# Carloop2-v3_1.net
KiCad netlist of a schematic drawn in EAGLE
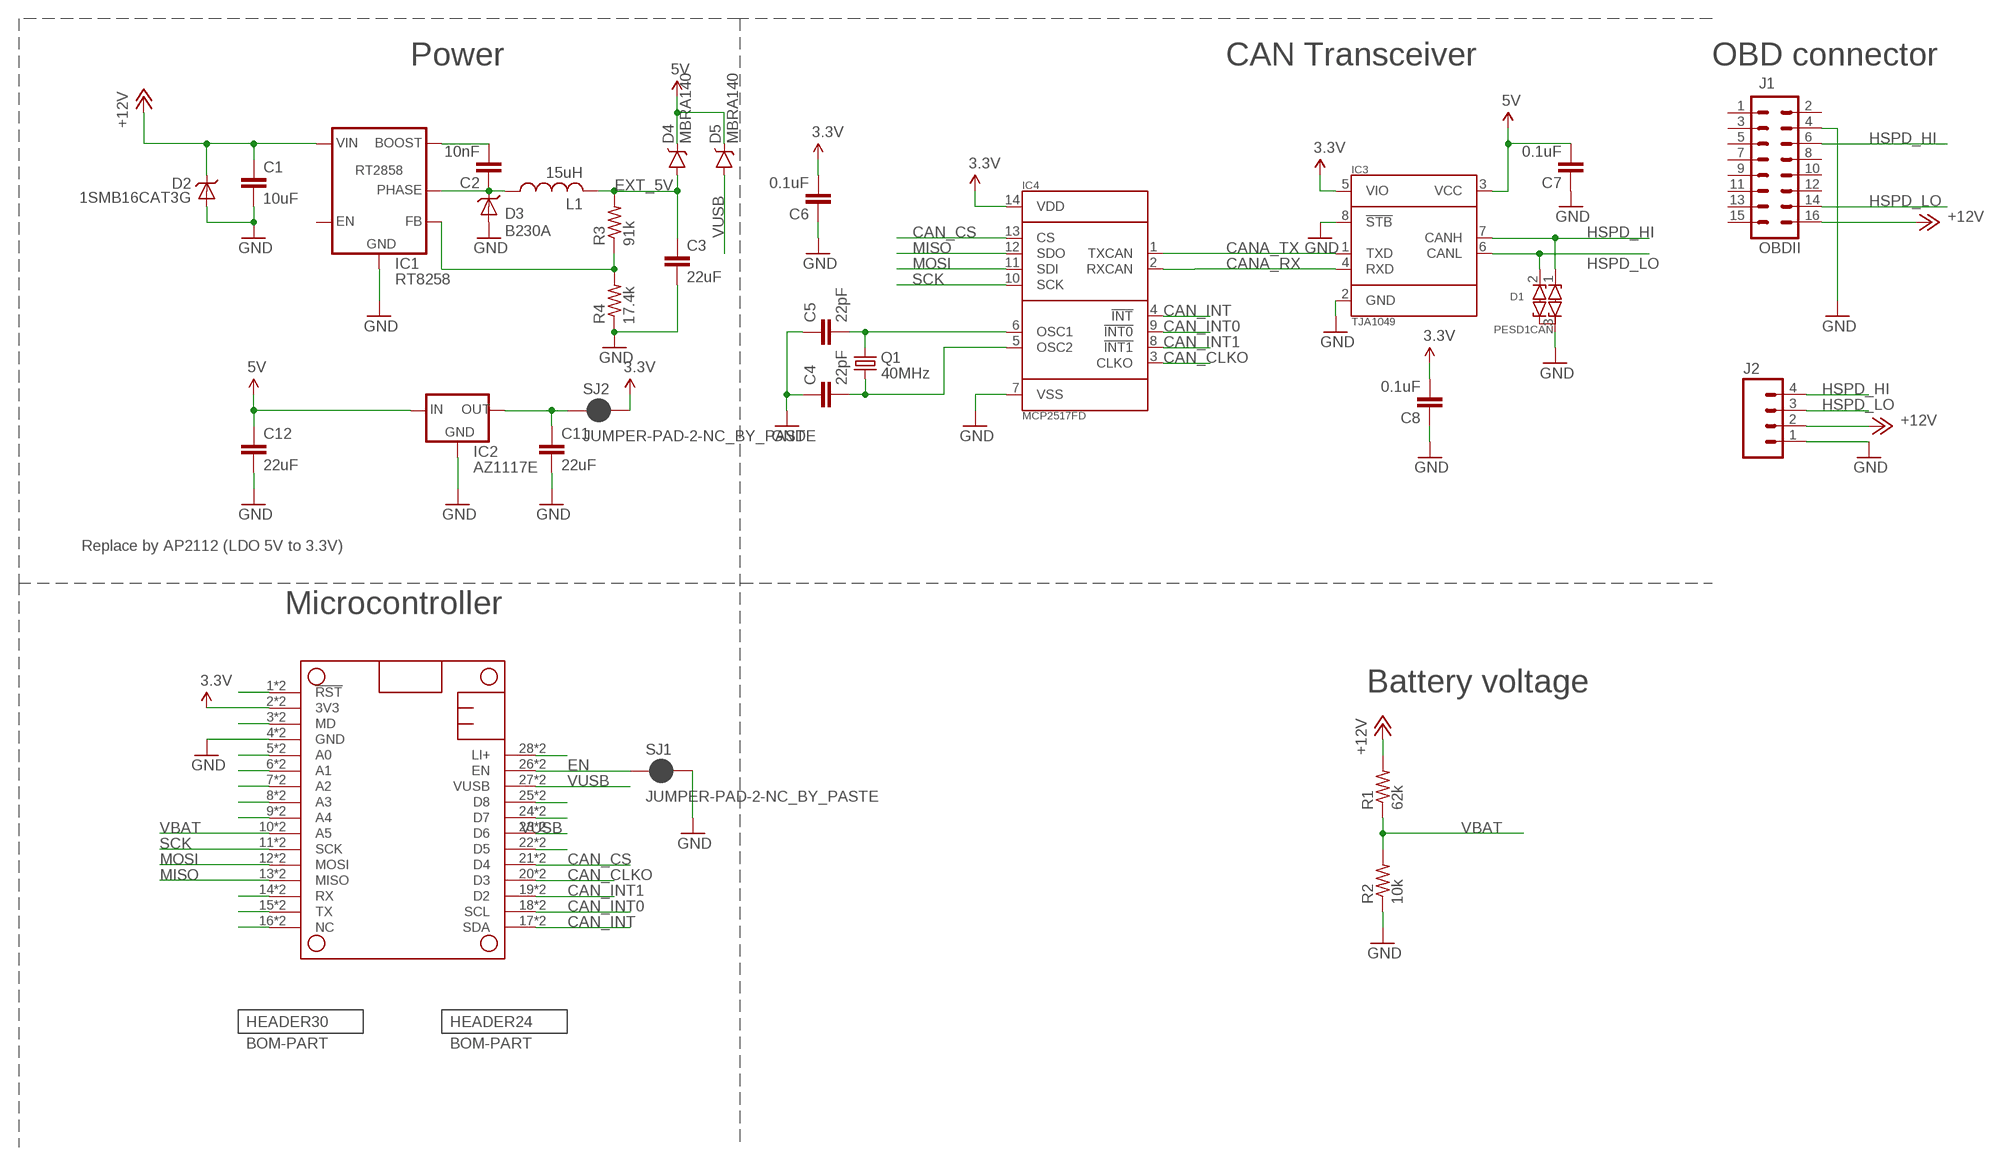
[diagram p0: schematic, sheet 1]

(export (version "E")
  (design (tool "Eeschema 10.0.6"))
  (components
    (comp (ref "C1")
      (value "10uF")
      (footprint "eagle-import:C1206")
      (fields (field (name "PARTNO") "C3216X7R1E106K160AB"))
      (libsource (lib "eagle-import") (part "C-EUC1206"))
    )
    (comp (ref "C2")
      (value "10nF")
      (footprint "eagle-import:C0603")
      (fields (field (name "PARTNO") "CGA3E2X8R1H103K080AA"))
      (libsource (lib "eagle-import") (part "C-EUC0603"))
    )
    (comp (ref "C3")
      (value "22uF")
      (footprint "eagle-import:C1206")
      (fields (field (name "PARTNO") "CL31X226KAHN3NE"))
      (libsource (lib "eagle-import") (part "C-EUC1206"))
    )
    (comp (ref "C4")
      (value "22pF")
      (footprint "eagle-import:C0603")
      (fields (field (name "PARTNO") "CC0603KRX7R9BB223"))
      (libsource (lib "eagle-import") (part "C-EUC0603"))
    )
    (comp (ref "C5")
      (value "22pF")
      (footprint "eagle-import:C0603")
      (fields (field (name "PARTNO") "CC0603KRX7R9BB223"))
      (libsource (lib "eagle-import") (part "C-EUC0603"))
    )
    (comp (ref "C6")
      (value "0.1uF")
      (footprint "eagle-import:C0603")
      (fields (field (name "PARTNO") "CC0603JRX7R7BB104"))
      (libsource (lib "eagle-import") (part "C-EUC0603"))
    )
    (comp (ref "C7")
      (value "0.1uF")
      (footprint "eagle-import:C0603")
      (fields (field (name "PARTNO") "CC0603JRX7R7BB104"))
      (libsource (lib "eagle-import") (part "C-EUC0603"))
    )
    (comp (ref "C8")
      (value "0.1uF")
      (footprint "eagle-import:C0603")
      (fields (field (name "PARTNO") "CC0603JRX7R7BB104"))
      (libsource (lib "eagle-import") (part "C-EUC0603"))
    )
    (comp (ref "C11")
      (value "22uF")
      (footprint "eagle-import:C1206")
      (fields (field (name "PARTNO") "CL31X226KAHN3NE"))
      (libsource (lib "eagle-import") (part "C-EUC1206"))
    )
    (comp (ref "C12")
      (value "22uF")
      (footprint "eagle-import:C1206")
      (fields (field (name "PARTNO") "CL31X226KAHN3NE"))
      (libsource (lib "eagle-import") (part "C-EUC1206"))
    )
    (comp (ref "D1")
      (value "PESD1CAN")
      (footprint "eagle-import:SOT23")
      (fields (field (name "PARTNO") "PESD1CAN-215"))
      (libsource (lib "eagle-import") (part "DIODE_ESD_DUAL-SOT-23"))
    )
    (comp (ref "D2")
      (value "1SMB16CAT3G")
      (footprint "eagle-import:SMB-DIODE")
      (libsource (lib "eagle-import") (part "DIODE-TVS-SMB"))
    )
    (comp (ref "D3")
      (value "B230A")
      (footprint "eagle-import:DO-214AA")
      (fields (field (name "PARTNO") "B230A-13-F"))
      (libsource (lib "eagle-import") (part "DIODE-SCHOTTKY"))
    )
    (comp (ref "D4")
      (value "MBRA140")
      (footprint "eagle-import:SMA-DIODE")
      (fields (field (name "PARTNO") "MBRA140T3G"))
      (libsource (lib "eagle-import") (part "MBRA140"))
    )
    (comp (ref "D5")
      (value "MBRA140")
      (footprint "eagle-import:SMA-DIODE")
      (fields (field (name "PARTNO") "MBRA140T3G"))
      (libsource (lib "eagle-import") (part "MBRA140"))
    )
    (comp (ref "IC1")
      (value "RT8258")
      (footprint "eagle-import:SOT-23-6")
      (fields (field (name "PARTNO") "RT8258GJ6"))
      (libsource (lib "eagle-import") (part "RT8258"))
    )
    (comp (ref "IC2")
      (value "AZ1117E")
      (footprint "eagle-import:SOT223")
      (fields (field (name "PARTNO") "AZ1117EH-3.3TRG1"))
      (libsource (lib "eagle-import") (part "AZ1117E"))
    )
    (comp (ref "IC3")
      (value "TJA1049")
      (footprint "eagle-import:SO8")
      (fields (field (name "PARTNO") "TJA1049T-118"))
      (libsource (lib "eagle-import") (part "TJA1049"))
    )
    (comp (ref "IC4")
      (value "MCP2517FD")
      (footprint "eagle-import:SOIC-14")
      (fields (field (name "PARTNO") "MCP2517FD-H/SL"))
      (libsource (lib "eagle-import") (part "MCP2517FD"))
    )
    (comp (ref "IC5")
      (value "PARTICLE_MESH_SMTDUAL")
      (footprint "eagle-import:FEATHERWING_SMT2")
      (libsource (lib "eagle-import") (part "PARTICLE_MESH_SMTDUAL"))
    )
    (comp (ref "J1")
      (value "OBDII")
      (footprint "eagle-import:OBDII-COMTECH")
      (fields (field (name "PARTNO") "OBD-II"))
      (libsource (lib "eagle-import") (part "M08X2-OBDII-COMTECH"))
    )
    (comp (ref "J2")
      (value "M04SCREW")
      (footprint "eagle-import:SCREWTERMINAL-3.5MM-4")
      (fields (field (name "PARTNO") "OSTTE040104"))
      (libsource (lib "eagle-import") (part "M04SCREW"))
    )
    (comp (ref "L1")
      (value "15uH")
      (footprint "eagle-import:NR8040")
      (fields (field (name "PARTNO") "NR8040T150M"))
      (libsource (lib "eagle-import") (part "L-US"))
    )
    (comp (ref "Q1")
      (value "40MHz")
      (footprint "eagle-import:CRYSTAL-SMD-5X3")
      (fields (field (name "PARTNO") "ECS-400-12-30B-AGM-TR"))
      (libsource (lib "eagle-import") (part "CRYSTAL5X3"))
    )
    (comp (ref "R1")
      (value "62k")
      (footprint "eagle-import:R0603")
      (fields (field (name "PARTNO") "ERA-3AEB623V"))
      (libsource (lib "eagle-import") (part "R-US_R0603"))
    )
    (comp (ref "R2")
      (value "10k")
      (footprint "eagle-import:R0603")
      (fields (field (name "PARTNO") "ERA-3AED103V"))
      (libsource (lib "eagle-import") (part "R-US_R0603"))
    )
    (comp (ref "R3")
      (value "91k")
      (footprint "eagle-import:R0603")
      (fields (field (name "PARTNO") "ERA-3ARB913V"))
      (libsource (lib "eagle-import") (part "R-US_R0603"))
    )
    (comp (ref "R4")
      (value "17.4k")
      (footprint "eagle-import:R0603")
      (fields (field (name "PARTNO") "ERJ-3EKF1742V"))
      (libsource (lib "eagle-import") (part "R-US_R0603"))
    )
    (comp (ref "SJ1")
      (value "JUMPER-PAD-2-NC_BY_PASTE")
      (footprint "eagle-import:PAD-JUMPER-2-NC_BY_PASTE_YES_SILK")
      (libsource (lib "eagle-import") (part "JUMPER-PAD-2-NC_BY_PASTE"))
    )
    (comp (ref "SJ2")
      (value "JUMPER-PAD-2-NC_BY_PASTE")
      (footprint "eagle-import:PAD-JUMPER-2-NC_BY_PASTE_YES_SILK")
      (libsource (lib "eagle-import") (part "JUMPER-PAD-2-NC_BY_PASTE"))
    )
  )
  (nets
    (net (code "1") (name "+12V") (class "Default")
      (node (ref "C1") (pin "1") (pinfunction "1_1") (pintype "passive"))
      (node (ref "D2") (pin "C") (pinfunction "C_C") (pintype "passive"))
      (node (ref "IC1") (pin "5") (pinfunction "VIN_5") (pintype "input"))
      (node (ref "J1") (pin "16") (pinfunction "16_16") (pintype "passive"))
      (node (ref "J2") (pin "2") (pinfunction "2_2") (pintype "passive"))
      (node (ref "R1") (pin "2") (pinfunction "2_2") (pintype "passive"))
    )
    (net (code "2") (name "/CANA_RX") (class "Default")
      (node (ref "IC3") (pin "4") (pinfunction "RXD_4") (pintype "bidirectional"))
      (node (ref "IC4") (pin "2") (pinfunction "RXCAN_2") (pintype "bidirectional"))
    )
    (net (code "3") (name "/CANA_TX") (class "Default")
      (node (ref "IC3") (pin "1") (pinfunction "TXD_1") (pintype "bidirectional"))
      (node (ref "IC4") (pin "1") (pinfunction "TXCAN_1") (pintype "bidirectional"))
    )
    (net (code "4") (name "/CAN_CLKO") (class "Default")
      (node (ref "IC4") (pin "3") (pinfunction "CLKO_3") (pintype "bidirectional"))
      (node (ref "IC5") (pin "20") (pinfunction "D3_20") (pintype "bidirectional"))
      (node (ref "IC5") (pin "20'") (pinfunction "D3_20'") (pintype "bidirectional"))
    )
    (net (code "5") (name "/CAN_CS") (class "Default")
      (node (ref "IC4") (pin "13") (pinfunction "CS_13") (pintype "bidirectional"))
      (node (ref "IC5") (pin "21") (pinfunction "D4_21") (pintype "bidirectional"))
      (node (ref "IC5") (pin "21'") (pinfunction "D4_21'") (pintype "bidirectional"))
    )
    (net (code "6") (name "/CAN_INT") (class "Default")
      (node (ref "IC4") (pin "4") (pinfunction "~{INT}_4") (pintype "bidirectional"))
      (node (ref "IC5") (pin "17") (pinfunction "SDA_17") (pintype "bidirectional"))
      (node (ref "IC5") (pin "17'") (pinfunction "SDA_17'") (pintype "bidirectional"))
    )
    (net (code "7") (name "/CAN_INT0") (class "Default")
      (node (ref "IC4") (pin "9") (pinfunction "~{INT0}_9") (pintype "bidirectional"))
      (node (ref "IC5") (pin "18") (pinfunction "SCL_18") (pintype "bidirectional"))
      (node (ref "IC5") (pin "18'") (pinfunction "SCL_18'") (pintype "bidirectional"))
    )
    (net (code "8") (name "/CAN_INT1") (class "Default")
      (node (ref "IC4") (pin "8") (pinfunction "~{INT1}_8") (pintype "bidirectional"))
      (node (ref "IC5") (pin "19") (pinfunction "D2_19") (pintype "bidirectional"))
      (node (ref "IC5") (pin "19'") (pinfunction "D2_19'") (pintype "bidirectional"))
    )
    (net (code "9") (name "/EN") (class "Default")
      (node (ref "IC5") (pin "26") (pinfunction "EN_26") (pintype "passive"))
      (node (ref "IC5") (pin "26'") (pinfunction "EN_26'") (pintype "passive"))
      (node (ref "SJ1") (pin "1") (pinfunction "1_1") (pintype "passive"))
    )
    (net (code "10") (name "/EXT_5V") (class "Default")
      (node (ref "C3") (pin "1") (pinfunction "1_1") (pintype "passive"))
      (node (ref "D4") (pin "A") (pinfunction "A_A") (pintype "passive"))
      (node (ref "L1") (pin "P$2") (pinfunction "2_P$2") (pintype "passive"))
      (node (ref "R3") (pin "2") (pinfunction "2_2") (pintype "passive"))
    )
    (net (code "11") (name "/HSPD_HI") (class "Default")
      (node (ref "D1") (pin "1") (pinfunction "C1_1") (pintype "power_in"))
      (node (ref "IC3") (pin "7") (pinfunction "CANH_7") (pintype "bidirectional"))
      (node (ref "J1") (pin "6") (pinfunction "6_6") (pintype "passive"))
      (node (ref "J2") (pin "4") (pinfunction "4_4") (pintype "passive"))
    )
    (net (code "12") (name "/HSPD_LO") (class "Default")
      (node (ref "D1") (pin "2") (pinfunction "C2_2") (pintype "power_in"))
      (node (ref "IC3") (pin "6") (pinfunction "CANL_6") (pintype "bidirectional"))
      (node (ref "J1") (pin "14") (pinfunction "14_14") (pintype "passive"))
      (node (ref "J2") (pin "3") (pinfunction "3_3") (pintype "passive"))
    )
    (net (code "13") (name "/MISO") (class "Default")
      (node (ref "IC4") (pin "12") (pinfunction "SDO_12") (pintype "bidirectional"))
      (node (ref "IC5") (pin "13") (pinfunction "MISO_13") (pintype "bidirectional"))
      (node (ref "IC5") (pin "13'") (pinfunction "MISO_13'") (pintype "bidirectional"))
    )
    (net (code "14") (name "/MOSI") (class "Default")
      (node (ref "IC4") (pin "11") (pinfunction "SDI_11") (pintype "bidirectional"))
      (node (ref "IC5") (pin "12") (pinfunction "MOSI_12") (pintype "bidirectional"))
      (node (ref "IC5") (pin "12'") (pinfunction "MOSI_12'") (pintype "bidirectional"))
    )
    (net (code "15") (name "/SCK") (class "Default")
      (node (ref "IC4") (pin "10") (pinfunction "SCK_10") (pintype "bidirectional"))
      (node (ref "IC5") (pin "11") (pinfunction "SCK_11") (pintype "bidirectional"))
      (node (ref "IC5") (pin "11'") (pinfunction "SCK_11'") (pintype "bidirectional"))
    )
    (net (code "16") (name "/VBAT") (class "Default")
      (node (ref "IC5") (pin "10") (pinfunction "A5_10") (pintype "bidirectional"))
      (node (ref "IC5") (pin "10'") (pinfunction "A5_10'") (pintype "bidirectional"))
      (node (ref "R1") (pin "1") (pinfunction "1_1") (pintype "passive"))
      (node (ref "R2") (pin "2") (pinfunction "2_2") (pintype "passive"))
    )
    (net (code "17") (name "/VUSB") (class "Default")
      (node (ref "D5") (pin "A") (pinfunction "A_A") (pintype "passive"))
      (node (ref "IC5") (pin "27") (pinfunction "VUSB_27") (pintype "power_in"))
      (node (ref "IC5") (pin "27'") (pinfunction "VUSB_27'") (pintype "power_in"))
    )
    (net (code "18") (name "3.3V") (class "Default")
      (node (ref "C6") (pin "2") (pinfunction "2_2") (pintype "passive"))
      (node (ref "C8") (pin "2") (pinfunction "2_2") (pintype "passive"))
      (node (ref "IC3") (pin "5") (pinfunction "VIO_5") (pintype "bidirectional"))
      (node (ref "IC4") (pin "14") (pinfunction "VDD_14") (pintype "bidirectional"))
      (node (ref "IC5") (pin "2") (pinfunction "3V3_2") (pintype "power_in"))
      (node (ref "IC5") (pin "2'") (pinfunction "3V3_2'") (pintype "power_in"))
      (node (ref "SJ2") (pin "2") (pinfunction "2_2") (pintype "passive"))
    )
    (net (code "19") (name "5V") (class "Default")
      (node (ref "C12") (pin "1") (pinfunction "1_1") (pintype "passive"))
      (node (ref "C7") (pin "2") (pinfunction "2_2") (pintype "passive"))
      (node (ref "D4") (pin "C") (pinfunction "C_C") (pintype "passive"))
      (node (ref "D5") (pin "C") (pinfunction "C_C") (pintype "passive"))
      (node (ref "IC2") (pin "1") (pinfunction "IN_1") (pintype "input"))
      (node (ref "IC3") (pin "3") (pinfunction "VCC_3") (pintype "bidirectional"))
    )
    (net (code "20") (name "GND") (class "Default")
      (node (ref "C1") (pin "2") (pinfunction "2_2") (pintype "passive"))
      (node (ref "C11") (pin "2") (pinfunction "2_2") (pintype "passive"))
      (node (ref "C12") (pin "2") (pinfunction "2_2") (pintype "passive"))
      (node (ref "C3") (pin "2") (pinfunction "2_2") (pintype "passive"))
      (node (ref "C4") (pin "1") (pinfunction "1_1") (pintype "passive"))
      (node (ref "C5") (pin "1") (pinfunction "1_1") (pintype "passive"))
      (node (ref "C6") (pin "1") (pinfunction "1_1") (pintype "passive"))
      (node (ref "C7") (pin "1") (pinfunction "1_1") (pintype "passive"))
      (node (ref "C8") (pin "1") (pinfunction "1_1") (pintype "passive"))
      (node (ref "D1") (pin "3") (pinfunction "COM_3") (pintype "power_in"))
      (node (ref "D2") (pin "A") (pinfunction "A_A") (pintype "passive"))
      (node (ref "D3") (pin "+") (pinfunction "A_+") (pintype "passive"))
      (node (ref "IC1") (pin "2") (pinfunction "GND_2") (pintype "input"))
      (node (ref "IC2") (pin "2") (pinfunction "GND_2") (pintype "input"))
      (node (ref "IC3") (pin "2") (pinfunction "GND_2") (pintype "bidirectional"))
      (node (ref "IC3") (pin "8") (pinfunction "~{STB}_8") (pintype "bidirectional"))
      (node (ref "IC4") (pin "7") (pinfunction "VSS_7") (pintype "bidirectional"))
      (node (ref "IC5") (pin "4") (pinfunction "GND_4") (pintype "power_in"))
      (node (ref "IC5") (pin "4'") (pinfunction "GND_4'") (pintype "power_in"))
      (node (ref "J1") (pin "4") (pinfunction "4_4") (pintype "passive"))
      (node (ref "J2") (pin "1") (pinfunction "1_1") (pintype "passive"))
      (node (ref "R2") (pin "1") (pinfunction "1_1") (pintype "passive"))
      (node (ref "R4") (pin "1") (pinfunction "1_1") (pintype "passive"))
      (node (ref "SJ1") (pin "2") (pinfunction "2_2") (pintype "passive"))
    )
    (net (code "21") (name "Net-(D3-C)") (class "Default")
      (node (ref "C2") (pin "1") (pinfunction "1_1") (pintype "passive"))
      (node (ref "D3") (pin "-") (pinfunction "C_-") (pintype "passive"))
      (node (ref "IC1") (pin "6") (pinfunction "PHASE_6") (pintype "passive"))
      (node (ref "L1") (pin "P$1") (pinfunction "1_P$1") (pintype "passive"))
    )
    (net (code "22") (name "Net-(IC1-BOOST)") (class "Default")
      (node (ref "C2") (pin "2") (pinfunction "2_2") (pintype "passive"))
      (node (ref "IC1") (pin "1") (pinfunction "BOOST_1") (pintype "passive"))
    )
    (net (code "23") (name "Net-(IC1-FB)") (class "Default")
      (node (ref "IC1") (pin "3") (pinfunction "FB_3") (pintype "passive"))
      (node (ref "R3") (pin "1") (pinfunction "1_1") (pintype "passive"))
      (node (ref "R4") (pin "2") (pinfunction "2_2") (pintype "passive"))
    )
    (net (code "24") (name "Net-(IC2-OUT)") (class "Default")
      (node (ref "C11") (pin "1") (pinfunction "1_1") (pintype "passive"))
      (node (ref "IC2") (pin "3") (pinfunction "OUT_3") (pintype "passive"))
      (node (ref "SJ2") (pin "1") (pinfunction "1_1") (pintype "passive"))
    )
    (net (code "25") (name "Net-(IC4-OSC1)") (class "Default")
      (node (ref "C5") (pin "2") (pinfunction "2_2") (pintype "passive"))
      (node (ref "IC4") (pin "6") (pinfunction "OSC1_6") (pintype "bidirectional"))
      (node (ref "Q1") (pin "3") (pinfunction "2_3") (pintype "passive"))
    )
    (net (code "26") (name "Net-(IC4-OSC2)") (class "Default")
      (node (ref "C4") (pin "2") (pinfunction "2_2") (pintype "passive"))
      (node (ref "IC4") (pin "5") (pinfunction "OSC2_5") (pintype "bidirectional"))
      (node (ref "Q1") (pin "1") (pinfunction "1_1") (pintype "passive"))
    )
    (net (code "27") (name "Net-(IC5-A0-Pad5')") (class "Default")
      (node (ref "IC5") (pin "5") (pinfunction "A0_5") (pintype "bidirectional"))
      (node (ref "IC5") (pin "5'") (pinfunction "A0_5'") (pintype "bidirectional"))
    )
    (net (code "28") (name "Net-(IC5-A1-Pad6')") (class "Default")
      (node (ref "IC5") (pin "6") (pinfunction "A1_6") (pintype "bidirectional"))
      (node (ref "IC5") (pin "6'") (pinfunction "A1_6'") (pintype "bidirectional"))
    )
    (net (code "29") (name "Net-(IC5-A2-Pad7')") (class "Default")
      (node (ref "IC5") (pin "7") (pinfunction "A2_7") (pintype "bidirectional"))
      (node (ref "IC5") (pin "7'") (pinfunction "A2_7'") (pintype "bidirectional"))
    )
    (net (code "30") (name "Net-(IC5-A3-Pad8')") (class "Default")
      (node (ref "IC5") (pin "8") (pinfunction "A3_8") (pintype "bidirectional"))
      (node (ref "IC5") (pin "8'") (pinfunction "A3_8'") (pintype "bidirectional"))
    )
    (net (code "31") (name "Net-(IC5-A4-Pad9')") (class "Default")
      (node (ref "IC5") (pin "9") (pinfunction "A4_9") (pintype "bidirectional"))
      (node (ref "IC5") (pin "9'") (pinfunction "A4_9'") (pintype "bidirectional"))
    )
    (net (code "32") (name "Net-(IC5-D5-Pad22')") (class "Default")
      (node (ref "IC5") (pin "22") (pinfunction "D5_22") (pintype "bidirectional"))
      (node (ref "IC5") (pin "22'") (pinfunction "D5_22'") (pintype "bidirectional"))
    )
    (net (code "33") (name "Net-(IC5-D6-Pad23')") (class "Default")
      (node (ref "IC5") (pin "23") (pinfunction "D6_23") (pintype "bidirectional"))
      (node (ref "IC5") (pin "23'") (pinfunction "D6_23'") (pintype "bidirectional"))
    )
    (net (code "34") (name "Net-(IC5-D7-Pad24')") (class "Default")
      (node (ref "IC5") (pin "24") (pinfunction "D7_24") (pintype "bidirectional"))
      (node (ref "IC5") (pin "24'") (pinfunction "D7_24'") (pintype "bidirectional"))
    )
    (net (code "35") (name "Net-(IC5-D8-Pad25')") (class "Default")
      (node (ref "IC5") (pin "25") (pinfunction "D8_25") (pintype "bidirectional"))
      (node (ref "IC5") (pin "25'") (pinfunction "D8_25'") (pintype "bidirectional"))
    )
    (net (code "36") (name "Net-(IC5-LI+-Pad28')") (class "Default")
      (node (ref "IC5") (pin "28") (pinfunction "LI+_28") (pintype "power_in"))
      (node (ref "IC5") (pin "28'") (pinfunction "LI+_28'") (pintype "power_in"))
    )
    (net (code "37") (name "Net-(IC5-MD-Pad3')") (class "Default")
      (node (ref "IC5") (pin "3") (pinfunction "MD_3") (pintype "bidirectional"))
      (node (ref "IC5") (pin "3'") (pinfunction "MD_3'") (pintype "bidirectional"))
    )
    (net (code "38") (name "Net-(IC5-NC-Pad16')") (class "Default")
      (node (ref "IC5") (pin "16") (pinfunction "NC_16") (pintype "passive"))
      (node (ref "IC5") (pin "16'") (pinfunction "NC_16'") (pintype "passive"))
    )
    (net (code "39") (name "Net-(IC5-RX-Pad14')") (class "Default")
      (node (ref "IC5") (pin "14") (pinfunction "RX_14") (pintype "bidirectional"))
      (node (ref "IC5") (pin "14'") (pinfunction "RX_14'") (pintype "bidirectional"))
    )
    (net (code "40") (name "Net-(IC5-TX-Pad15')") (class "Default")
      (node (ref "IC5") (pin "15") (pinfunction "TX_15") (pintype "bidirectional"))
      (node (ref "IC5") (pin "15'") (pinfunction "TX_15'") (pintype "bidirectional"))
    )
    (net (code "41") (name "Net-(IC5-~{RST}-Pad1')") (class "Default")
      (node (ref "IC5") (pin "1") (pinfunction "~{RST}_1") (pintype "input"))
      (node (ref "IC5") (pin "1'") (pinfunction "~{RST}_1'") (pintype "input"))
    )
    (net (code "42") (name "unconnected-(IC1-EN-Pad4)") (class "Default")
      (node (ref "IC1") (pin "4") (pinfunction "EN_4") (pintype "input"))
    )
    (net (code "43") (name "unconnected-(J1-Pad1)") (class "Default")
      (node (ref "J1") (pin "1") (pinfunction "1_1") (pintype "passive"))
    )
    (net (code "44") (name "unconnected-(J1-Pad2)") (class "Default")
      (node (ref "J1") (pin "2") (pinfunction "2_2") (pintype "passive"))
    )
    (net (code "45") (name "unconnected-(J1-Pad3)") (class "Default")
      (node (ref "J1") (pin "3") (pinfunction "3_3") (pintype "passive"))
    )
    (net (code "46") (name "unconnected-(J1-Pad5)") (class "Default")
      (node (ref "J1") (pin "5") (pinfunction "5_5") (pintype "passive"))
    )
    (net (code "47") (name "unconnected-(J1-Pad7)") (class "Default")
      (node (ref "J1") (pin "7") (pinfunction "7_7") (pintype "passive"))
    )
    (net (code "48") (name "unconnected-(J1-Pad8)") (class "Default")
      (node (ref "J1") (pin "8") (pinfunction "8_8") (pintype "passive"))
    )
    (net (code "49") (name "unconnected-(J1-Pad9)") (class "Default")
      (node (ref "J1") (pin "9") (pinfunction "9_9") (pintype "passive"))
    )
    (net (code "50") (name "unconnected-(J1-Pad10)") (class "Default")
      (node (ref "J1") (pin "10") (pinfunction "10_10") (pintype "passive"))
    )
    (net (code "51") (name "unconnected-(J1-Pad11)") (class "Default")
      (node (ref "J1") (pin "11") (pinfunction "11_11") (pintype "passive"))
    )
    (net (code "52") (name "unconnected-(J1-Pad12)") (class "Default")
      (node (ref "J1") (pin "12") (pinfunction "12_12") (pintype "passive"))
    )
    (net (code "53") (name "unconnected-(J1-Pad13)") (class "Default")
      (node (ref "J1") (pin "13") (pinfunction "13_13") (pintype "passive"))
    )
    (net (code "54") (name "unconnected-(J1-Pad15)") (class "Default")
      (node (ref "J1") (pin "15") (pinfunction "15_15") (pintype "passive"))
    )
  )
)
